# ME3116_5V.net
KiCad netlist of a schematic drawn in Altium Designer
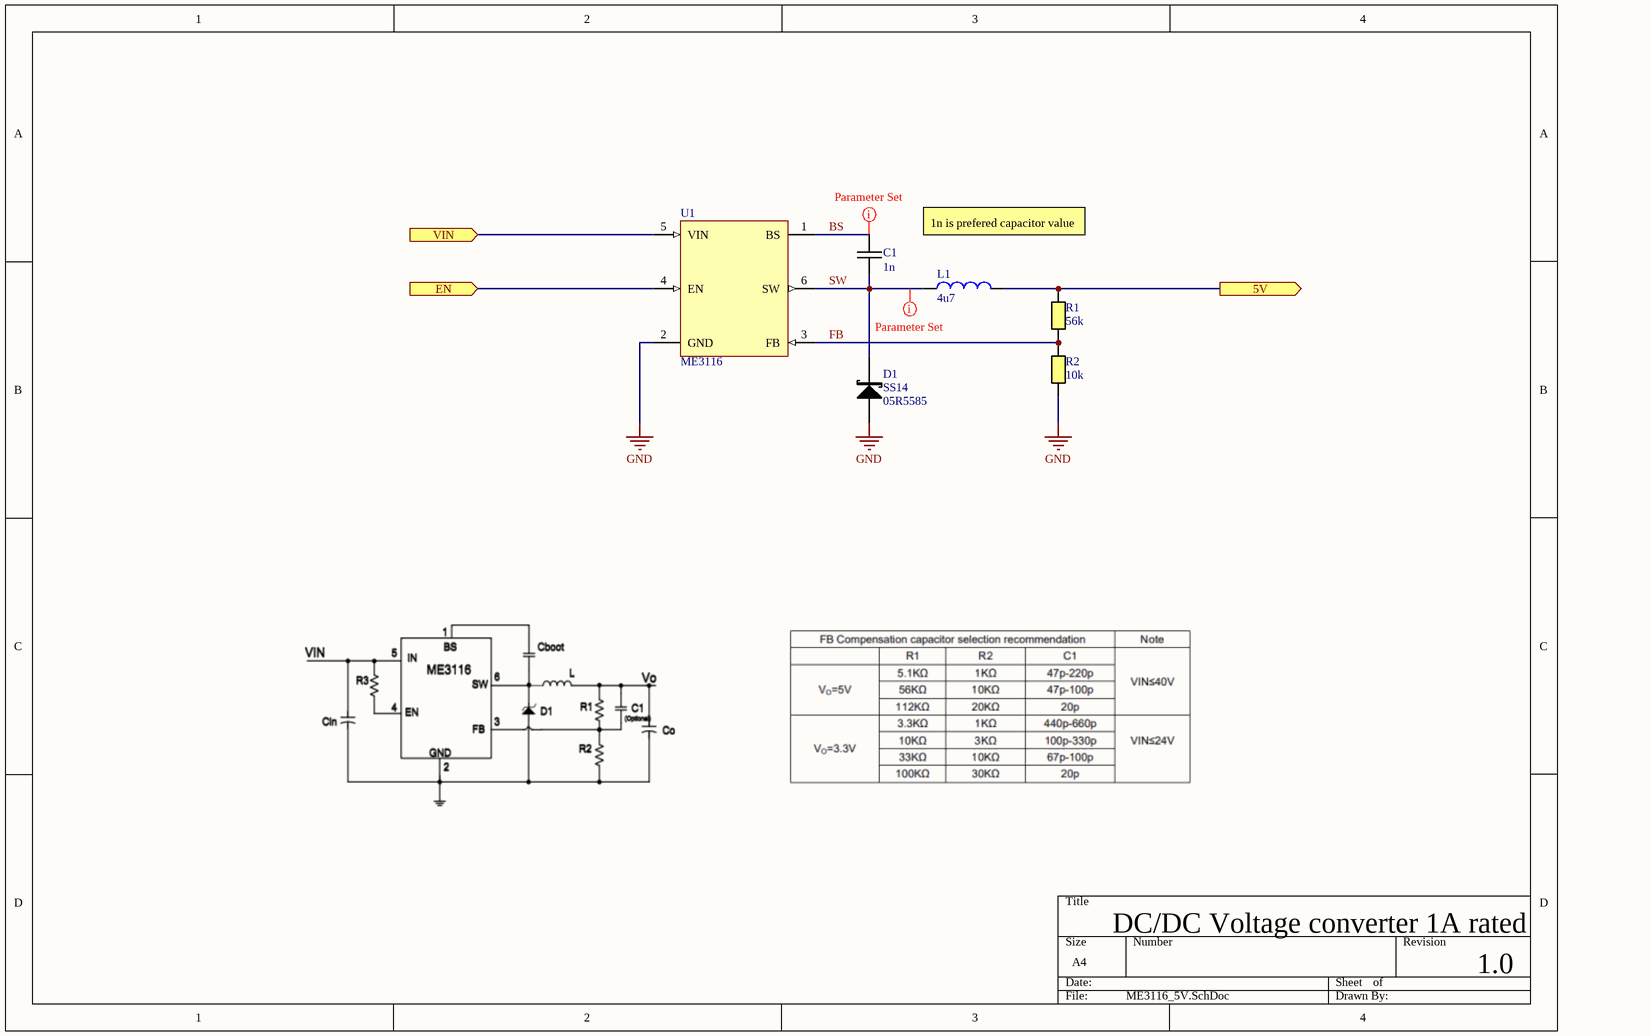
[diagram p0: ME3116_5V.SchDoc]

(export (version "E")
  (design (tool "Eeschema 10.0.6"))
  (components
    (comp (ref "C1")
      (value "1n")
      (footprint "CAPC0603(1608)55_N")
      (description "Ceramic capacitor Medium density")
      (libsource (lib "Discrete") (part "Capacitor M"))
    )
    (comp (ref "D1")
      (value "SS14")
      (footprint "SMA")
      (description "Surface Mount Schottky Barrier Rectifier")
      (fields (field (name "SUPPLIER PART NUMBER 1") "05R5585"))
      (libsource (lib "Diodes") (part "SS14"))
    )
    (comp (ref "L1") (value "4u7") (footprint "CD32") (libsource (lib "Discrete") (part "Inductor")))
    (comp (ref "R1")
      (value "56k")
      (footprint "RESC0603(1608)_N")
      (description "Resistor Medium Density")
      (libsource (lib "Discrete") (part "Resistor M"))
    )
    (comp (ref "R2")
      (value "10k")
      (footprint "RESC0603(1608)_N")
      (description "Resistor Medium Density")
      (libsource (lib "Discrete") (part "Resistor M"))
    )
    (comp (ref "U1")
      (value "ME3116")
      (footprint "SOT23-6")
      (description "The ME3116 is PWM DC/DC buck (step-down) regulators.")
      (libsource (lib "VoltageRegulators") (part "ME3116"))
    )
  )
  (nets
    (net (code "1") (name "/5V") (class "Default")
      (node (ref "L1") (pin "2") (pinfunction "2_2") (pintype "passive"))
      (node (ref "R1") (pin "2") (pinfunction "2_2") (pintype "passive"))
    )
    (net (code "2") (name "/BS") (class "Default")
      (node (ref "C1") (pin "1") (pinfunction "1_1") (pintype "passive"))
      (node (ref "U1") (pin "1") (pinfunction "BS_1") (pintype "passive"))
    )
    (net (code "3") (name "/EN") (class "Default")
      (node (ref "U1") (pin "4") (pinfunction "EN_4") (pintype "input"))
    )
    (net (code "4") (name "/FB") (class "Default")
      (node (ref "R1") (pin "1") (pinfunction "1_1") (pintype "passive"))
      (node (ref "R2") (pin "2") (pinfunction "2_2") (pintype "passive"))
      (node (ref "U1") (pin "3") (pinfunction "FB_3") (pintype "input"))
    )
    (net (code "5") (name "/SW") (class "Default")
      (node (ref "C1") (pin "2") (pinfunction "2_2") (pintype "passive"))
      (node (ref "D1") (pin "K") (pinfunction "K_K") (pintype "passive"))
      (node (ref "L1") (pin "1") (pinfunction "1_1") (pintype "passive"))
      (node (ref "U1") (pin "6") (pinfunction "SW_6") (pintype "output"))
    )
    (net (code "6") (name "/VIN") (class "Default")
      (node (ref "U1") (pin "5") (pinfunction "VIN_5") (pintype "input"))
    )
    (net (code "7") (name "GND") (class "Default")
      (node (ref "D1") (pin "A") (pinfunction "A_A") (pintype "passive"))
      (node (ref "R2") (pin "1") (pinfunction "1_1") (pintype "passive"))
      (node (ref "U1") (pin "2") (pinfunction "GND_2") (pintype "power_in"))
    )
  )
)
